# Main.net
KiCad netlist of a schematic drawn in Altium Designer
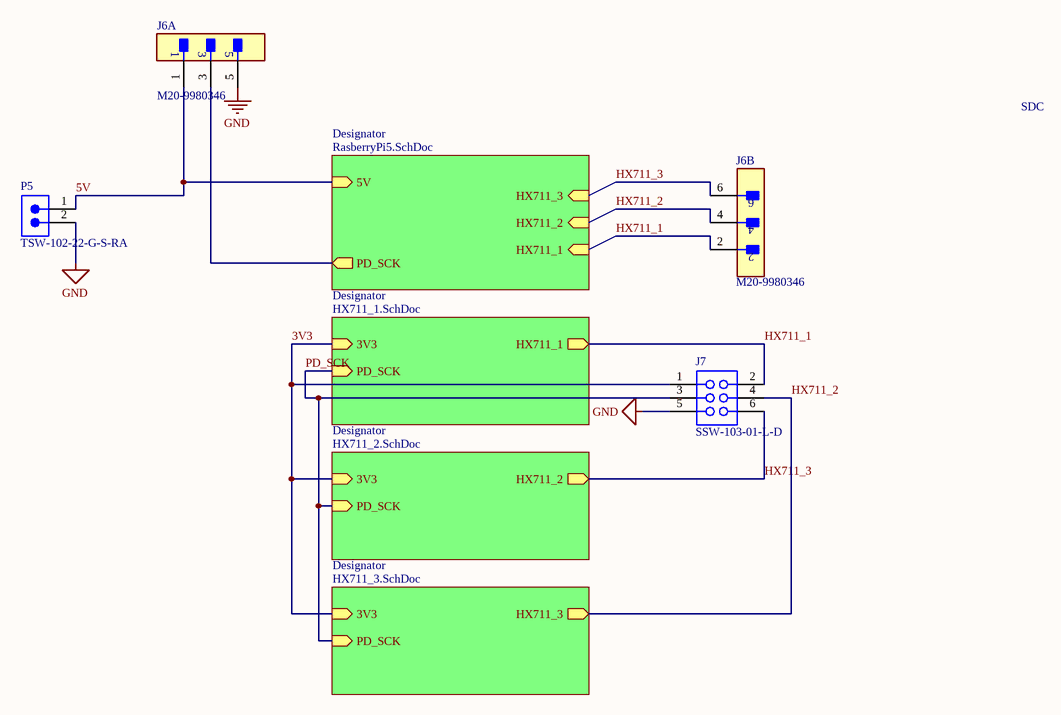
[diagram p0: Main.SchDoc]

(export (version "E")
  (design (tool "Eeschema 10.0.6"))
  (components
    (comp (ref "J6")
      (value "M20-9980346")
      (footprint "FP-M20-9980346-MFG")
      (description "CONN HEADER VERT 6POS 2.54MM")
      (fields
        (field (name "MANUFACTURER") "Harwin")
        (field (name "OCTOPART") "https://octopart.com/m20-9980346-harwin-5436545")
      )
      (libsource (lib "Altium Content Vault") (part "2654a11fb13586ecb194516b1c997bc"))
    )
    (comp (ref "J7")
      (value "SSW-103-01-L-D")
      (footprint "SMTC-SSW-103-01-X-D")
      (description "SQ Post Socket, Through-hole, Vertical, -55 to 125 degC, 2.54 mm Pitch, 6-Pin, Female, RoHS")
      (fields (field (name "MANUFACTURER") "Samtec"))
      (libsource (lib "Altium Content Vault") (part "SMTC-SSW-103-01-X-D"))
    )
    (comp (ref "P5")
      (value "TSW-102-22-G-S-RA")
      (footprint "SMTC-TSW-102-22-X-S-RA")
      (fields (field (name "MANUFACTURER") "Samtec"))
      (libsource (lib "Altium Content Vault") (part "SMTC-TSW-102-X-X-S-X"))
    )
  )
  (nets
    (net (code "1") (name "/3V3") (class "Default")
      (node (ref "J7") (pin "1") (pinfunction "1_1") (pintype "passive"))
    )
    (net (code "2") (name "/5V") (class "Default")
      (node (ref "J6") (pin "1") (pinfunction "1_1") (pintype "passive"))
      (node (ref "P5") (pin "1") (pinfunction "1_1") (pintype "passive"))
    )
    (net (code "3") (name "/HX711_1") (class "Default")
      (node (ref "J6") (pin "2") (pinfunction "2_2") (pintype "passive"))
      (node (ref "J7") (pin "2") (pinfunction "2_2") (pintype "passive"))
    )
    (net (code "4") (name "/HX711_2") (class "Default")
      (node (ref "J6") (pin "4") (pinfunction "4_4") (pintype "passive"))
      (node (ref "J7") (pin "4") (pinfunction "4_4") (pintype "passive"))
    )
    (net (code "5") (name "/HX711_3") (class "Default")
      (node (ref "J6") (pin "6") (pinfunction "6_6") (pintype "passive"))
      (node (ref "J7") (pin "6") (pinfunction "6_6") (pintype "passive"))
    )
    (net (code "6") (name "/PD_SCK") (class "Default")
      (node (ref "J7") (pin "3") (pinfunction "3_3") (pintype "passive"))
    )
    (net (code "7") (name "/PD_SCK_1") (class "Default")
      (node (ref "J6") (pin "3") (pinfunction "3_3") (pintype "passive"))
    )
    (net (code "8") (name "GND") (class "Default")
      (node (ref "J6") (pin "5") (pinfunction "5_5") (pintype "passive"))
      (node (ref "J7") (pin "5") (pinfunction "5_5") (pintype "passive"))
      (node (ref "P5") (pin "2") (pinfunction "2_2") (pintype "passive"))
    )
  )
)
